# FE_Channel.net
KiCad netlist of a schematic drawn in Altium Designer
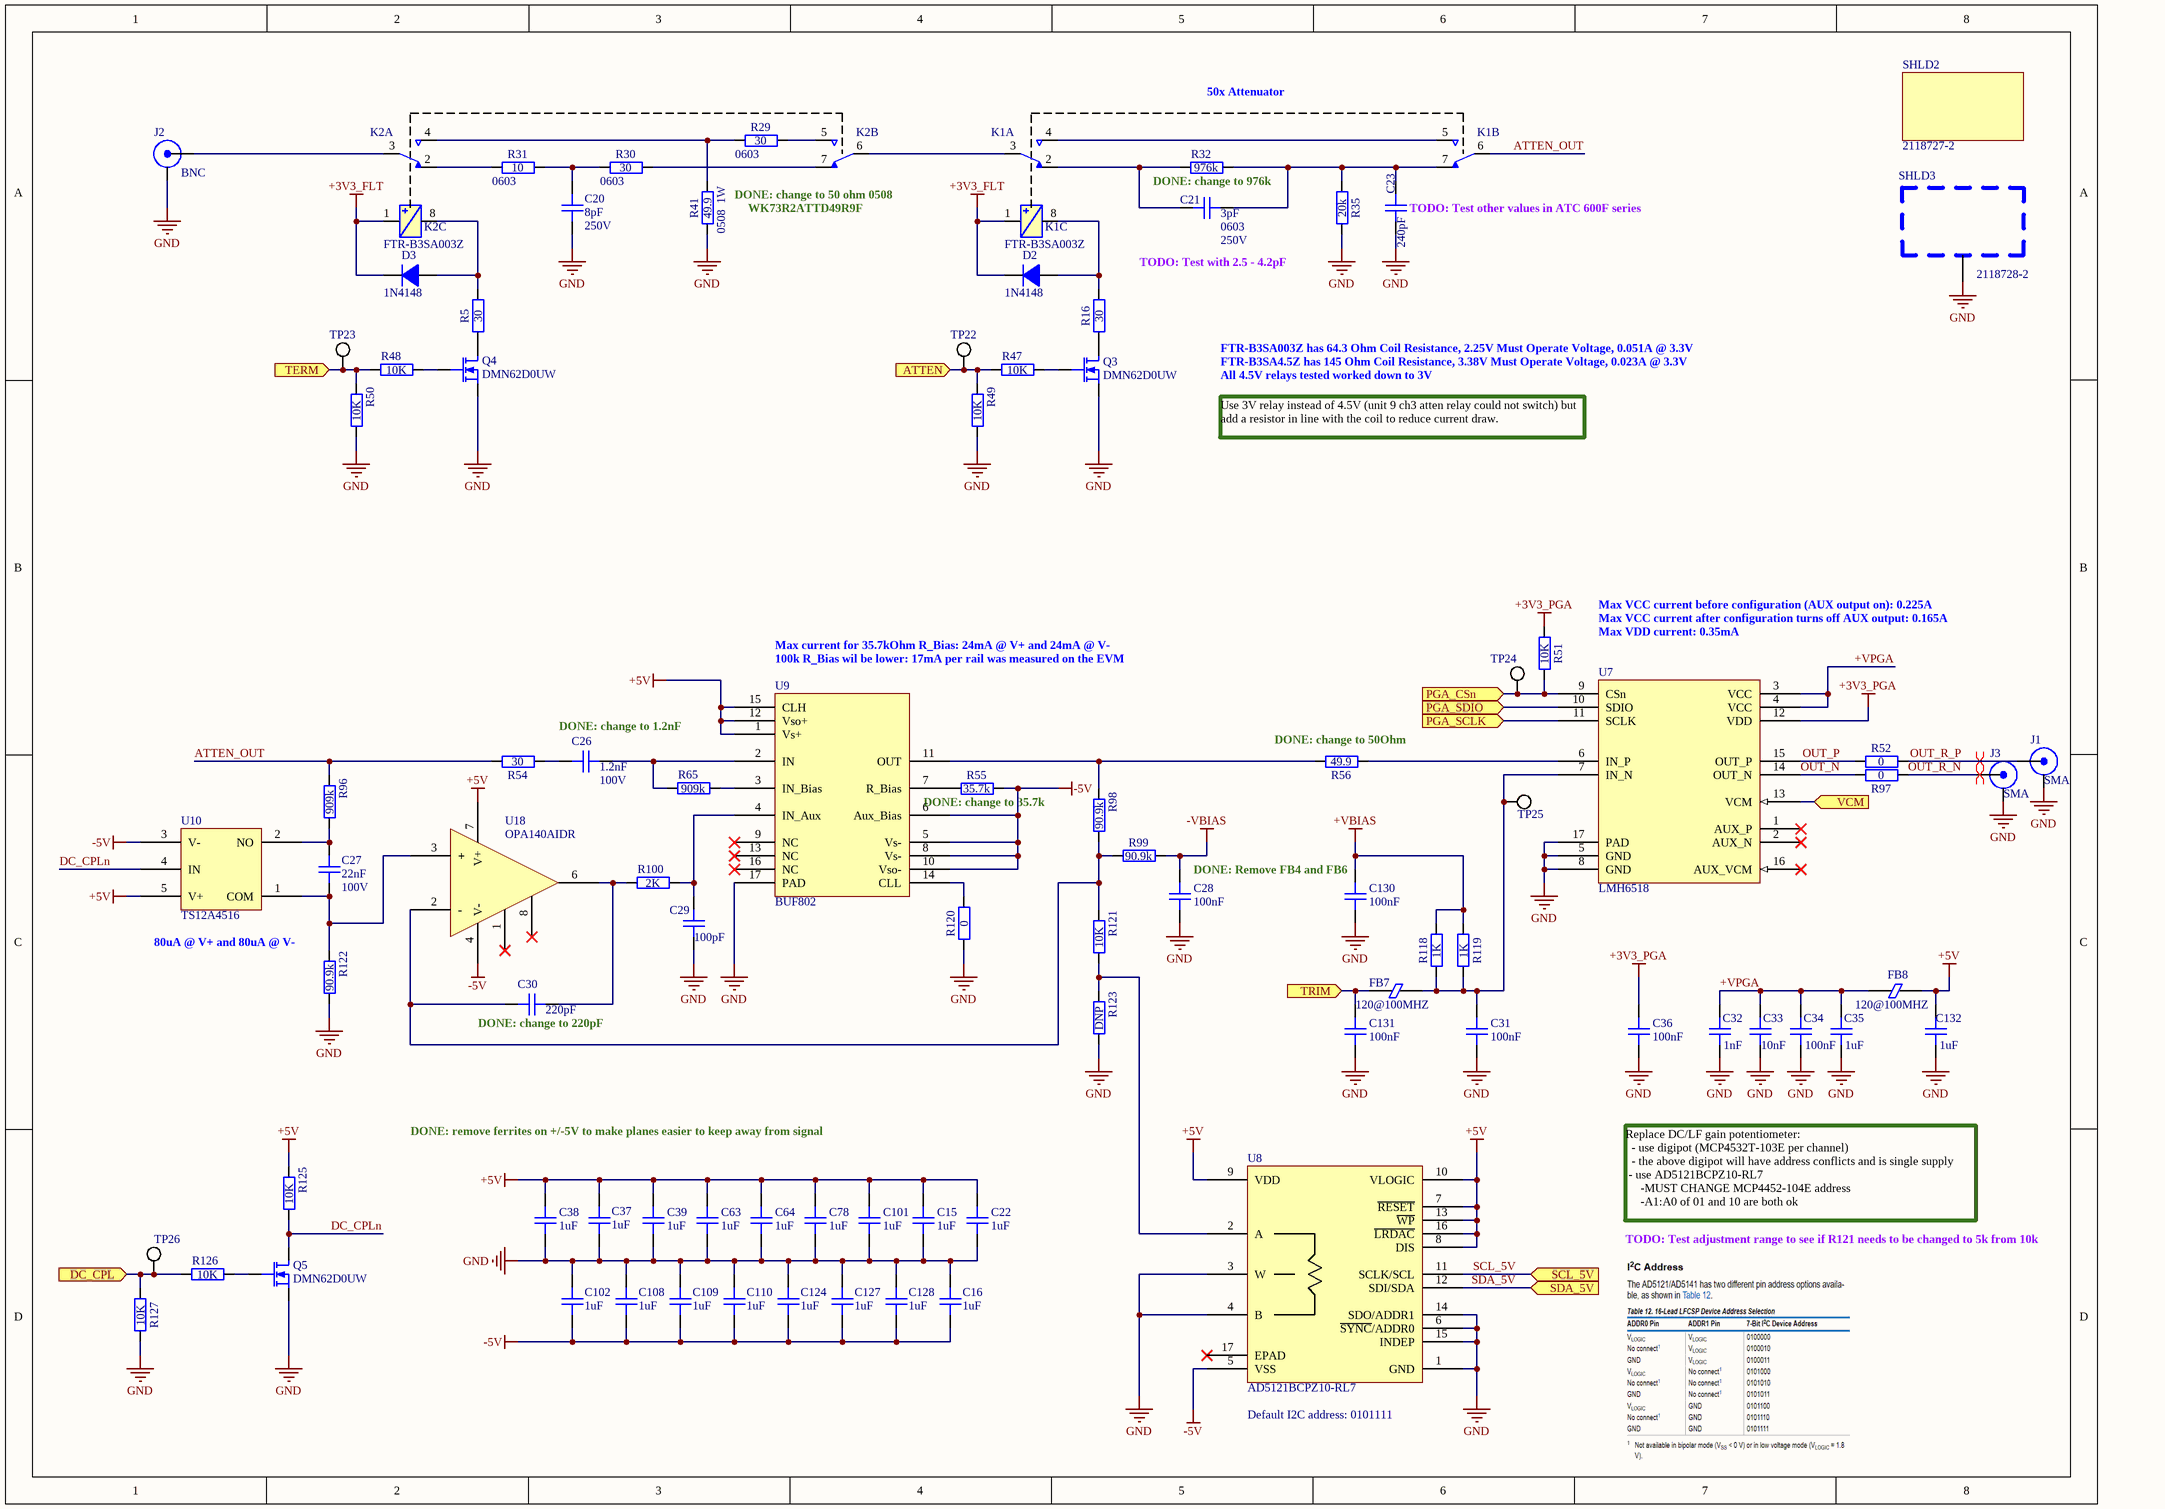
[diagram p0: FE_Channel.SchDoc]

(export (version "E")
  (design (tool "Eeschema 10.0.6"))
  (components
    (comp (ref "C15")
      (value "1uF")
      (footprint "GEN_C_0402")
      (fields
        (field (name "MANUFACTURER") "Murata")
        (field (name "MANUFACTURER PART NUMBER") "GRM155R61E105KA12D")
      )
      (libsource (lib "DSO") (part "CAP 1uF 25V X5R 0402"))
    )
    (comp (ref "C16")
      (value "1uF")
      (footprint "GEN_C_0402")
      (fields
        (field (name "MANUFACTURER") "Murata")
        (field (name "MANUFACTURER PART NUMBER") "GRM155R61E105KA12D")
      )
      (libsource (lib "DSO") (part "CAP 1uF 25V X5R 0402"))
    )
    (comp (ref "C20")
      (value "8pF")
      (footprint "GEN_C_0603")
      (fields
        (field (name "MANUFACTURER") "KEMET")
        (field (name "MANUFACTURER PART NUMBER") "CBR06C809BAGAC")
        (field (name "VOLTAGE RATING") "250V")
      )
      (libsource (lib "DSO") (part "CAP 8pF 250V C0G 0603"))
    )
    (comp (ref "C21")
      (value "3pF")
      (footprint "GEN_C_0603")
      (fields
        (field (name "PACKAGE") "0603")
        (field (name "VOLTAGE RATING") "250V")
        (field (name "MANUFACTURER") "KEMET")
        (field (name "MANUFACTURER PART NUMBER") "CBR06C309BAGAC")
      )
      (libsource (lib "DSO") (part "CAP 3pF 250V C0G 0603"))
    )
    (comp (ref "C22")
      (value "1uF")
      (footprint "GEN_C_0402")
      (fields
        (field (name "MANUFACTURER") "Murata")
        (field (name "MANUFACTURER PART NUMBER") "GRM155R61E105KA12D")
      )
      (libsource (lib "DSO") (part "CAP 1uF 25V X5R 0402"))
    )
    (comp (ref "C23")
      (value "240pF")
      (footprint "GEN_C_0805")
      (fields
        (field (name "MANUFACTURER") "Kyocera AVX")
        (field (name "MANUFACTURER PART NUMBER") "600F241FT250XT")
      )
      (libsource (lib "DSO") (part "CAP 240pF 250V C0G 0805"))
    )
    (comp (ref "C26")
      (value "1.2nF")
      (footprint "GEN_C_0603")
      (fields
        (field (name "VOLTAGE RATING") "100V")
        (field (name "MANUFACTURER") "Murata")
        (field (name "MANUFACTURER PART NUMBER") "GCM1885C2A122FA16D")
      )
      (libsource (lib "DSO") (part "CAP 1.2nF 100V C0G 0603"))
    )
    (comp (ref "C27")
      (value "22nF")
      (footprint "GEN_C_0603")
      (fields
        (field (name "VOLTAGE RATING") "100V")
        (field (name "MANUFACTURER") "Murata")
        (field (name "MANUFACTURER PART NUMBER") "GCM188R72A223KA37D")
      )
      (libsource (lib "DSO") (part "CAP 22nF 100V X7R 0603"))
    )
    (comp (ref "C28")
      (value "100nF")
      (footprint "GEN_C_0402")
      (fields
        (field (name "HOUSE PART NUMBER") "C-100nF-0402-002")
        (field (name "MANUFACTURER") "Murata")
        (field (name "MANUFACTURER PART NUMBER") "GCM155R71C104KA55D")
      )
      (libsource (lib "DSO") (part "CAP 100nF 16V X7R 0402"))
    )
    (comp (ref "C29")
      (value "100pF")
      (footprint "GEN_C_0402")
      (fields
        (field (name "MANUFACTURER") "Murata")
        (field (name "MANUFACTURER PART NUMBER") "GCM1555C1H101FA16D")
      )
      (libsource (lib "DSO") (part "CAP 100pF 50V C0G 0402"))
    )
    (comp (ref "C30")
      (value "220pF")
      (footprint "GEN_C_0402")
      (fields
        (field (name "MANUFACTURER") "Murata")
        (field (name "MANUFACTURER PART NUMBER") "GCM1555C1H221FA16J")
      )
      (libsource (lib "DSO") (part "CAP 220pF 50V C0G 0402"))
    )
    (comp (ref "C31")
      (value "100nF")
      (footprint "GEN_C_0402")
      (fields
        (field (name "HOUSE PART NUMBER") "C-100nF-0402-002")
        (field (name "MANUFACTURER") "Murata")
        (field (name "MANUFACTURER PART NUMBER") "GCM155R71C104KA55D")
      )
      (libsource (lib "DSO") (part "CAP 100nF 16V X7R 0402"))
    )
    (comp (ref "C32")
      (value "1nF")
      (footprint "GEN_C_0402")
      (fields
        (field (name "MANUFACTURER") "Murata")
        (field (name "MANUFACTURER PART NUMBER") "GRM1555C1H102FA01D")
      )
      (libsource (lib "DSO") (part "CAP 1nF 50V C0G 0402"))
    )
    (comp (ref "C33")
      (value "10nF")
      (footprint "GEN_C_0402")
      (fields
        (field (name "HOUSE PART NUMBER") "C-10nF-0402-002")
        (field (name "MANUFACTURER") "Murata")
        (field (name "MANUFACTURER PART NUMBER") "GRM155R71H103KA88J")
      )
      (libsource (lib "DSO") (part "CAP 10nF 50V X7R 0402"))
    )
    (comp (ref "C34")
      (value "100nF")
      (footprint "GEN_C_0402")
      (fields
        (field (name "HOUSE PART NUMBER") "C-100nF-0402-002")
        (field (name "MANUFACTURER") "Murata")
        (field (name "MANUFACTURER PART NUMBER") "GCM155R71C104KA55D")
      )
      (libsource (lib "DSO") (part "CAP 100nF 16V X7R 0402"))
    )
    (comp (ref "C35")
      (value "1uF")
      (footprint "GEN_C_0402")
      (fields
        (field (name "MANUFACTURER") "Murata")
        (field (name "MANUFACTURER PART NUMBER") "GRM155R61E105KA12D")
      )
      (libsource (lib "DSO") (part "CAP 1uF 25V X5R 0402"))
    )
    (comp (ref "C36")
      (value "100nF")
      (footprint "GEN_C_0402")
      (fields
        (field (name "HOUSE PART NUMBER") "C-100nF-0402-002")
        (field (name "MANUFACTURER") "Murata")
        (field (name "MANUFACTURER PART NUMBER") "GCM155R71C104KA55D")
      )
      (libsource (lib "DSO") (part "CAP 100nF 16V X7R 0402"))
    )
    (comp (ref "C37")
      (value "1uF")
      (footprint "GEN_C_0402")
      (fields
        (field (name "MANUFACTURER") "Murata")
        (field (name "MANUFACTURER PART NUMBER") "GRM155R61E105KA12D")
      )
      (libsource (lib "DSO") (part "CAP 1uF 25V X5R 0402"))
    )
    (comp (ref "C38")
      (value "1uF")
      (footprint "GEN_C_0402")
      (fields
        (field (name "MANUFACTURER") "Murata")
        (field (name "MANUFACTURER PART NUMBER") "GRM155R61E105KA12D")
      )
      (libsource (lib "DSO") (part "CAP 1uF 25V X5R 0402"))
    )
    (comp (ref "C39")
      (value "1uF")
      (footprint "GEN_C_0402")
      (fields
        (field (name "MANUFACTURER") "Murata")
        (field (name "MANUFACTURER PART NUMBER") "GRM155R61E105KA12D")
      )
      (libsource (lib "DSO") (part "CAP 1uF 25V X5R 0402"))
    )
    (comp (ref "C63")
      (value "1uF")
      (footprint "GEN_C_0402")
      (fields
        (field (name "MANUFACTURER") "Murata")
        (field (name "MANUFACTURER PART NUMBER") "GRM155R61E105KA12D")
      )
      (libsource (lib "DSO") (part "CAP 1uF 25V X5R 0402"))
    )
    (comp (ref "C64")
      (value "1uF")
      (footprint "GEN_C_0402")
      (fields
        (field (name "MANUFACTURER") "Murata")
        (field (name "MANUFACTURER PART NUMBER") "GRM155R61E105KA12D")
      )
      (libsource (lib "DSO") (part "CAP 1uF 25V X5R 0402"))
    )
    (comp (ref "C78")
      (value "1uF")
      (footprint "GEN_C_0402")
      (fields
        (field (name "MANUFACTURER") "Murata")
        (field (name "MANUFACTURER PART NUMBER") "GRM155R61E105KA12D")
      )
      (libsource (lib "DSO") (part "CAP 1uF 25V X5R 0402"))
    )
    (comp (ref "C101")
      (value "1uF")
      (footprint "GEN_C_0402")
      (fields
        (field (name "MANUFACTURER") "Murata")
        (field (name "MANUFACTURER PART NUMBER") "GRM155R61E105KA12D")
      )
      (libsource (lib "DSO") (part "CAP 1uF 25V X5R 0402"))
    )
    (comp (ref "C102")
      (value "1uF")
      (footprint "GEN_C_0402")
      (fields
        (field (name "MANUFACTURER") "Murata")
        (field (name "MANUFACTURER PART NUMBER") "GRM155R61E105KA12D")
      )
      (libsource (lib "DSO") (part "CAP 1uF 25V X5R 0402"))
    )
    (comp (ref "C108")
      (value "1uF")
      (footprint "GEN_C_0402")
      (fields
        (field (name "MANUFACTURER") "Murata")
        (field (name "MANUFACTURER PART NUMBER") "GRM155R61E105KA12D")
      )
      (libsource (lib "DSO") (part "CAP 1uF 25V X5R 0402"))
    )
    (comp (ref "C109")
      (value "1uF")
      (footprint "GEN_C_0402")
      (fields
        (field (name "MANUFACTURER") "Murata")
        (field (name "MANUFACTURER PART NUMBER") "GRM155R61E105KA12D")
      )
      (libsource (lib "DSO") (part "CAP 1uF 25V X5R 0402"))
    )
    (comp (ref "C110")
      (value "1uF")
      (footprint "GEN_C_0402")
      (fields
        (field (name "MANUFACTURER") "Murata")
        (field (name "MANUFACTURER PART NUMBER") "GRM155R61E105KA12D")
      )
      (libsource (lib "DSO") (part "CAP 1uF 25V X5R 0402"))
    )
    (comp (ref "C124")
      (value "1uF")
      (footprint "GEN_C_0402")
      (fields
        (field (name "MANUFACTURER") "Murata")
        (field (name "MANUFACTURER PART NUMBER") "GRM155R61E105KA12D")
      )
      (libsource (lib "DSO") (part "CAP 1uF 25V X5R 0402"))
    )
    (comp (ref "C127")
      (value "1uF")
      (footprint "GEN_C_0402")
      (fields
        (field (name "MANUFACTURER") "Murata")
        (field (name "MANUFACTURER PART NUMBER") "GRM155R61E105KA12D")
      )
      (libsource (lib "DSO") (part "CAP 1uF 25V X5R 0402"))
    )
    (comp (ref "C128")
      (value "1uF")
      (footprint "GEN_C_0402")
      (fields
        (field (name "MANUFACTURER") "Murata")
        (field (name "MANUFACTURER PART NUMBER") "GRM155R61E105KA12D")
      )
      (libsource (lib "DSO") (part "CAP 1uF 25V X5R 0402"))
    )
    (comp (ref "C130")
      (value "100nF")
      (footprint "GEN_C_0402")
      (fields
        (field (name "HOUSE PART NUMBER") "C-100nF-0402-002")
        (field (name "MANUFACTURER") "Murata")
        (field (name "MANUFACTURER PART NUMBER") "GCM155R71C104KA55D")
      )
      (libsource (lib "DSO") (part "CAP 100nF 16V X7R 0402"))
    )
    (comp (ref "C131")
      (value "100nF")
      (footprint "GEN_C_0402")
      (fields
        (field (name "HOUSE PART NUMBER") "C-100nF-0402-002")
        (field (name "MANUFACTURER") "Murata")
        (field (name "MANUFACTURER PART NUMBER") "GCM155R71C104KA55D")
      )
      (libsource (lib "DSO") (part "CAP 100nF 16V X7R 0402"))
    )
    (comp (ref "C132")
      (value "1uF")
      (footprint "GEN_C_0402")
      (fields
        (field (name "MANUFACTURER") "Murata")
        (field (name "MANUFACTURER PART NUMBER") "GRM155R61E105KA12D")
      )
      (libsource (lib "DSO") (part "CAP 1uF 25V X5R 0402"))
    )
    (comp (ref "D2")
      (value "1N4148")
      (footprint "GEN_SOD_323")
      (fields (field (name "MANUFACTURER") "Diodes") (field (name "MANUFACTURER PART NUMBER") "1N4148WS-7-F"))
      (libsource (lib "DSO") (part "DIODE 1N4148"))
    )
    (comp (ref "D3")
      (value "1N4148")
      (footprint "GEN_SOD_323")
      (fields (field (name "MANUFACTURER") "Diodes") (field (name "MANUFACTURER PART NUMBER") "1N4148WS-7-F"))
      (libsource (lib "DSO") (part "DIODE 1N4148"))
    )
    (comp (ref "FB7")
      (value "120@100MHZ")
      (footprint "GEN_R_0402")
      (fields (field (name "HOUSE PART NUMBER") "BLM15PX121SN1D") (field (name "MANUFACTURER") "Murata"))
      (libsource (lib "DSO") (part "FERRITE BEAD 120 OHM 0402"))
    )
    (comp (ref "FB8")
      (value "120@100MHZ")
      (footprint "GEN_R_0402")
      (fields (field (name "HOUSE PART NUMBER") "BLM15PX121SN1D") (field (name "MANUFACTURER") "Murata"))
      (libsource (lib "DSO") (part "FERRITE BEAD 120 OHM 0402"))
    )
    (comp (ref "J1")
      (value "SMA")
      (footprint "MOL_0733910083")
      (fields (field (name "MANUFACTURER") "Molex") (field (name "MANUFACTURER PART NUMBER") "73100-0105"))
      (libsource (lib "DSO") (part "SMA JACK R/A"))
    )
    (comp (ref "J2")
      (value "BNC")
      (footprint "MOL_0731000105")
      (fields (field (name "MANUFACTURER") "Molex") (field (name "MANUFACTURER PART NUMBER") "73100-0105"))
      (libsource (lib "DSO") (part "BNC JACK R/A"))
    )
    (comp (ref "J3")
      (value "SMA")
      (footprint "MOL_0733910083")
      (fields (field (name "MANUFACTURER") "Molex") (field (name "MANUFACTURER PART NUMBER") "73100-0105"))
      (libsource (lib "DSO") (part "SMA JACK R/A"))
    )
    (comp (ref "K1")
      (value "FTR-B3SA003Z")
      (footprint "FUJ_FTR-B3SA")
      (fields (field (name "MANUFACTURER") "Fujitsu"))
      (libsource (lib "") (part "RELAY DPDT-NO FTR-B3SA003Z_1"))
    )
    (comp (ref "K2")
      (value "FTR-B3SA003Z")
      (footprint "FUJ_FTR-B3SA")
      (fields (field (name "MANUFACTURER") "Fujitsu"))
      (libsource (lib "") (part "RELAY DPDT-NO FTR-B3SA003Z_1"))
    )
    (comp (ref "Q3")
      (value "DMN62D0UW")
      (footprint "GEN_SOT_323")
      (fields (field (name "HOUSE PART NUMBER") "DMN62D0UW-7") (field (name "MANUFACTURER") "Diodes"))
      (libsource (lib "DSO") (part "NMOS DMN62D0UW"))
    )
    (comp (ref "Q4")
      (value "DMN62D0UW")
      (footprint "GEN_SOT_323")
      (fields (field (name "HOUSE PART NUMBER") "DMN62D0UW-7") (field (name "MANUFACTURER") "Diodes"))
      (libsource (lib "DSO") (part "NMOS DMN62D0UW"))
    )
    (comp (ref "Q5")
      (value "DMN62D0UW")
      (footprint "GEN_SOT_323")
      (fields (field (name "HOUSE PART NUMBER") "DMN62D0UW-7") (field (name "MANUFACTURER") "Diodes"))
      (libsource (lib "DSO") (part "NMOS DMN62D0UW"))
    )
    (comp (ref "R5")
      (value "30")
      (footprint "GEN_R_0603")
      (fields
        (field (name "TOLERANCE") "1%")
        (field (name "MANUFACTURER") "KOA Speer")
        (field (name "MANUFACTURER PART NUMBER") "SG73P1JTTD30R0F")
      )
      (libsource (lib "") (part "RES 30 OHM 1% 1/3W 0603_1"))
    )
    (comp (ref "R16")
      (value "30")
      (footprint "GEN_R_0603")
      (fields
        (field (name "TOLERANCE") "1%")
        (field (name "MANUFACTURER") "KOA Speer")
        (field (name "MANUFACTURER PART NUMBER") "SG73P1JTTD30R0F")
      )
      (libsource (lib "") (part "RES 30 OHM 1% 1/3W 0603_1"))
    )
    (comp (ref "R29")
      (value "30")
      (footprint "GEN_R_0603")
      (fields
        (field (name "TOLERANCE") "1%")
        (field (name "PACKAGE") "0603")
        (field (name "MANUFACTURER") "KOA Speer")
        (field (name "MANUFACTURER PART NUMBER") "SG73P1JTTD30R0F")
      )
      (libsource (lib "DSO") (part "RES 30 OHM 1% 1/3W 0603"))
    )
    (comp (ref "R30")
      (value "30")
      (footprint "GEN_R_0603")
      (fields
        (field (name "TOLERANCE") "1%")
        (field (name "PACKAGE") "0603")
        (field (name "MANUFACTURER") "KOA Speer")
        (field (name "MANUFACTURER PART NUMBER") "SG73P1JTTD30R0F")
      )
      (libsource (lib "DSO") (part "RES 30 OHM 1% 1/3W 0603"))
    )
    (comp (ref "R31")
      (value "10")
      (footprint "GEN_R_0603")
      (fields
        (field (name "TOLERANCE") "1%")
        (field (name "PACKAGE") "0603")
        (field (name "MANUFACTURER") "KOA Speer")
        (field (name "MANUFACTURER PART NUMBER") "SG73P1JTTD10R0F")
      )
      (libsource (lib "DSO") (part "RES 10 OHM 1% 1/3W 0603"))
    )
    (comp (ref "R32")
      (value "976k")
      (footprint "GEN_R_0603")
      (fields
        (field (name "MANUFACTURER") "KOA Speer")
        (field (name "MANUFACTURER PART NUMBER") "RK73H1JTTD9763F")
        (field (name "TOLERANCE") "1%")
      )
      (libsource (lib "DSO") (part "RES 976k OHM 1% 1/10W 0603"))
    )
    (comp (ref "R35")
      (value "20k")
      (footprint "GEN_R_0402")
      (fields
        (field (name "TOLERANCE") "1%")
        (field (name "MANUFACTURER") "Yageo")
        (field (name "MANUFACTURER PART NUMBER") "RC0402FR-0720KL")
      )
      (libsource (lib "DSO") (part "RES 20K OHM 1% 1/16W 0402"))
    )
    (comp (ref "R41")
      (value "49.9")
      (footprint "GEN_R_0508")
      (fields
        (field (name "TOLERANCE") "1%")
        (field (name "PACKAGE") "0508")
        (field (name "MANUFACTURER") "KOA Speer")
        (field (name "MANUFACTURER PART NUMBER") "WK73R2ATTD49R9F")
        (field (name "POWER RATING") "1W")
      )
      (libsource (lib "DSO") (part "RES 49.9 OHM 1% 1W 0508"))
    )
    (comp (ref "R47")
      (value "10K")
      (footprint "GEN_R_0402")
      (fields
        (field (name "TOLERANCE") "1%")
        (field (name "MANUFACTURER") "Panasonic")
        (field (name "MANUFACTURER PART NUMBER") "ERJ-2RKF1002X")
      )
      (libsource (lib "") (part "RES 10K OHM 1% 1/10W 0402_1"))
    )
    (comp (ref "R48")
      (value "10K")
      (footprint "GEN_R_0402")
      (fields
        (field (name "TOLERANCE") "1%")
        (field (name "MANUFACTURER") "Panasonic")
        (field (name "MANUFACTURER PART NUMBER") "ERJ-2RKF1002X")
      )
      (libsource (lib "") (part "RES 10K OHM 1% 1/10W 0402_1"))
    )
    (comp (ref "R49")
      (value "10K")
      (footprint "GEN_R_0402")
      (fields
        (field (name "TOLERANCE") "1%")
        (field (name "MANUFACTURER") "Panasonic")
        (field (name "MANUFACTURER PART NUMBER") "ERJ-2RKF1002X")
      )
      (libsource (lib "DSO") (part "RES 10K OHM 1% 1/10W 0402"))
    )
    (comp (ref "R50")
      (value "10K")
      (footprint "GEN_R_0402")
      (fields
        (field (name "TOLERANCE") "1%")
        (field (name "MANUFACTURER") "Panasonic")
        (field (name "MANUFACTURER PART NUMBER") "ERJ-2RKF1002X")
      )
      (libsource (lib "DSO") (part "RES 10K OHM 1% 1/10W 0402"))
    )
    (comp (ref "R51")
      (value "10K")
      (footprint "GEN_R_0402")
      (fields
        (field (name "TOLERANCE") "1%")
        (field (name "MANUFACTURER") "Panasonic")
        (field (name "MANUFACTURER PART NUMBER") "ERJ-2RKF1002X")
      )
      (libsource (lib "DSO") (part "RES 10K OHM 1% 1/10W 0402"))
    )
    (comp (ref "R52")
      (value "0")
      (footprint "GEN_R_0402")
      (fields
        (field (name "MANUFACTURER") "Yageo")
        (field (name "MANUFACTURER PART NUMBER") "RC0402JR-070RL")
      )
      (libsource (lib "") (part "RES 0 OHM 1/16W 0402_1"))
    )
    (comp (ref "R54")
      (value "30")
      (footprint "GEN_R_0603")
      (fields
        (field (name "TOLERANCE") "1%")
        (field (name "MANUFACTURER") "KOA Speer")
        (field (name "MANUFACTURER PART NUMBER") "SG73P1JTTD30R0F")
      )
      (libsource (lib "DSO") (part "RES 30 OHM 1% 1/3W 0603"))
    )
    (comp (ref "R55")
      (value "35.7k")
      (footprint "GEN_R_0402")
      (fields
        (field (name "TOLERANCE") "1%")
        (field (name "MANUFACTURER") "Yageo")
        (field (name "MANUFACTURER PART NUMBER") "RC0402FR-0735K7L")
      )
      (libsource (lib "DSO") (part "RES 35.7K OHM 1% 1/16W 0402"))
    )
    (comp (ref "R56")
      (value "49.9")
      (footprint "GEN_R_0402")
      (fields
        (field (name "MANUFACTURER") "Yageo")
        (field (name "MANUFACTURER PART NUMBER") "RC0402FR-0749R9L")
        (field (name "TOLERANCE") "1%")
      )
      (libsource (lib "DSO") (part "RES 49.9 OHM 1% 1/10W 0402"))
    )
    (comp (ref "R65")
      (value "909k")
      (footprint "GEN_R_0402")
      (fields
        (field (name "TOLERANCE") "1%")
        (field (name "MANUFACTURER") "Yageo")
        (field (name "MANUFACTURER PART NUMBER") "RC0402FR-07909KL")
      )
      (libsource (lib "DSO") (part "RES 909K OHM 1% 1/16W 0402"))
    )
    (comp (ref "R96")
      (value "909k")
      (footprint "GEN_R_0402")
      (fields
        (field (name "TOLERANCE") "1%")
        (field (name "MANUFACTURER") "Yageo")
        (field (name "MANUFACTURER PART NUMBER") "RC0402FR-07909KL")
      )
      (libsource (lib "") (part "RES 909K OHM 1% 1/16W 0402_1"))
    )
    (comp (ref "R97")
      (value "0")
      (footprint "GEN_R_0402")
      (fields
        (field (name "MANUFACTURER") "Yageo")
        (field (name "MANUFACTURER PART NUMBER") "RC0402JR-070RL")
      )
      (libsource (lib "") (part "RES 0 OHM 1/16W 0402_1"))
    )
    (comp (ref "R98")
      (value "90.9k")
      (footprint "GEN_R_0402")
      (fields
        (field (name "TOLERANCE") "1%")
        (field (name "MANUFACTURER") "Yageo")
        (field (name "MANUFACTURER PART NUMBER") "RC0402FR-0790K9L")
      )
      (libsource (lib "") (part "RES 90.9K OHM 1% 1/16W 0402_1"))
    )
    (comp (ref "R99")
      (value "90.9k")
      (footprint "GEN_R_0402")
      (fields
        (field (name "TOLERANCE") "1%")
        (field (name "MANUFACTURER") "Yageo")
        (field (name "MANUFACTURER PART NUMBER") "RC0402FR-0790K9L")
      )
      (libsource (lib "DSO") (part "RES 90.9K OHM 1% 1/16W 0402"))
    )
    (comp (ref "R100")
      (value "2K")
      (footprint "GEN_R_0402")
      (fields
        (field (name "TOLERANCE") "1%")
        (field (name "MANUFACTURER") "Yageo")
        (field (name "MANUFACTURER PART NUMBER") "RC0402FR-072KL")
      )
      (libsource (lib "DSO") (part "RES 2K OHM 1% 1/16W 0402"))
    )
    (comp (ref "R118")
      (value "1K")
      (footprint "GEN_R_0402")
      (fields
        (field (name "TOLERANCE") "1%")
        (field (name "HOUSE PART NUMBER") "R-1K-0402-1%-001")
        (field (name "MANUFACTURER") "Yageo")
      )
      (libsource (lib "") (part "RES 1K OHM 1% 1/10W 0402_1"))
    )
    (comp (ref "R119")
      (value "1K")
      (footprint "GEN_R_0402")
      (fields
        (field (name "TOLERANCE") "1%")
        (field (name "HOUSE PART NUMBER") "R-1K-0402-1%-001")
        (field (name "MANUFACTURER") "Yageo")
      )
      (libsource (lib "DSO") (part "RES 1K OHM 1% 1/10W 0402"))
    )
    (comp (ref "R120")
      (value "0")
      (footprint "GEN_R_0402")
      (fields
        (field (name "MANUFACTURER") "Yageo")
        (field (name "MANUFACTURER PART NUMBER") "RC0402JR-070RL")
      )
      (libsource (lib "DSO") (part "RES 0 OHM 1/16W 0402"))
    )
    (comp (ref "R121")
      (value "10K")
      (footprint "GEN_R_0402")
      (fields
        (field (name "TOLERANCE") "1%")
        (field (name "MANUFACTURER") "Panasonic")
        (field (name "MANUFACTURER PART NUMBER") "ERJ-2RKF1002X")
      )
      (libsource (lib "DSO") (part "RES 10K OHM 1% 1/10W 0402"))
    )
    (comp (ref "R122")
      (value "90.9k")
      (footprint "GEN_R_0402")
      (fields
        (field (name "TOLERANCE") "1%")
        (field (name "MANUFACTURER") "Yageo")
        (field (name "MANUFACTURER PART NUMBER") "RC0402FR-0790K9L")
      )
      (libsource (lib "") (part "RES 90.9K OHM 1% 1/16W 0402_1"))
    )
    (comp (ref "R123")
      (value "DNP")
      (footprint "GEN_R_0402")
      (fields (field (name "TOLERANCE") "1%"))
      (libsource (lib "DSO") (part "RES DNP 0402"))
    )
    (comp (ref "R125")
      (value "10K")
      (footprint "GEN_R_0402")
      (fields
        (field (name "TOLERANCE") "1%")
        (field (name "MANUFACTURER") "Panasonic")
        (field (name "MANUFACTURER PART NUMBER") "ERJ-2RKF1002X")
      )
      (libsource (lib "DSO") (part "RES 10K OHM 1% 1/10W 0402"))
    )
    (comp (ref "R126")
      (value "10K")
      (footprint "GEN_R_0402")
      (fields
        (field (name "TOLERANCE") "1%")
        (field (name "MANUFACTURER") "Panasonic")
        (field (name "MANUFACTURER PART NUMBER") "ERJ-2RKF1002X")
      )
      (libsource (lib "") (part "RES 10K OHM 1% 1/10W 0402_1"))
    )
    (comp (ref "R127")
      (value "10K")
      (footprint "GEN_R_0402")
      (fields
        (field (name "TOLERANCE") "1%")
        (field (name "MANUFACTURER") "Panasonic")
        (field (name "MANUFACTURER PART NUMBER") "ERJ-2RKF1002X")
      )
      (libsource (lib "") (part "RES 10K OHM 1% 1/10W 0402_2"))
    )
    (comp (ref "SHLD2")
      (value "2118727-2")
      (fields (field (name "MANUFACTURER") "TE Connectivity AMP"))
      (libsource (lib "DSO") (part "SHIELD 2118727-2"))
    )
    (comp (ref "SHLD3")
      (value "2118728-2")
      (footprint "TE_2118728-2")
      (fields (field (name "MANUFACTURER") "TE Connectivity"))
      (libsource (lib "DSO") (part "SHIELD 2118728-2"))
    )
    (comp (ref "TP22") (value "PCB") (footprint "GEN_TP_PCB") (libsource (lib "DSO") (part "TP PCB 1mm")))
    (comp (ref "TP23") (value "PCB") (footprint "GEN_TP_PCB") (libsource (lib "DSO") (part "TP PCB 1mm")))
    (comp (ref "TP24") (value "PCB") (footprint "GEN_TP_PCB") (libsource (lib "DSO") (part "TP PCB 1mm")))
    (comp (ref "TP25") (value "PCB") (footprint "GEN_TP_PCB") (libsource (lib "DSO") (part "TP PCB 1mm")))
    (comp (ref "TP26") (value "PCB") (footprint "GEN_TP_PCB") (libsource (lib "DSO") (part "TP PCB 1mm")))
    (comp (ref "U7")
      (value "LMH6518")
      (footprint "TI_WQFN_RGH0016A")
      (fields
        (field (name "MANUFACTURER") "Texas Instruments")
        (field (name "MANUFACTURER PART NUMBER") "LMH6518SQE/NOPB")
      )
      (libsource (lib "DSO") (part "IC PGA LMH6518"))
    )
    (comp (ref "U8")
      (value "AD5121BCPZ10-RL7")
      (footprint "AD_QFN16_CP-16-22")
      (fields (field (name "MANUFACTURER") "Analog Devices"))
      (libsource (lib "DSO") (part "IC DIGIPOT SINGLE AD5121BCPZ10-RL7"))
    )
    (comp (ref "U9")
      (value "BUF802")
      (footprint "TI_VQFN_RGT0016C")
      (fields
        (field (name "MANUFACTURER") "Texas Instruments")
        (field (name "MANUFACTURER PART NUMBER") "BUF802IRGTR")
      )
      (libsource (lib "DSO") (part "IC BUFFER AMP BUF802"))
    )
    (comp (ref "U10")
      (value "TS12A4516")
      (footprint "GEN_SOT23_5_950_2900X1600X1450")
      (fields
        (field (name "MANUFACTURER") "Texas Instruments")
        (field (name "MANUFACTURER PART NUMBER") "TS12A4516DBVR")
      )
      (libsource (lib "DSO") (part "IC SWITCH SPST TS12A4516DBVR"))
    )
    (comp (ref "U18")
      (value "OPA140AIDR")
      (footprint "TI_SOIC8_D0008A")
      (fields (field (name "MANUFACTURER") "Texas Instruments"))
      (libsource (lib "DSO") (part "IC OPAMP OPA140"))
    )
  )
  (nets
    (net (code "1") (name "+3V3_FLT") (class "Default")
      (node (ref "D2") (pin "1") (pinfunction "K_1") (pintype "passive"))
      (node (ref "D3") (pin "1") (pinfunction "K_1") (pintype "passive"))
      (node (ref "K1") (pin "1") (pinfunction "1_1") (pintype "passive"))
      (node (ref "K2") (pin "1") (pinfunction "1_1") (pintype "passive"))
    )
    (net (code "2") (name "+3V3_PGA") (class "Default")
      (node (ref "C36") (pin "2") (pinfunction "2_2") (pintype "passive"))
      (node (ref "R51") (pin "2") (pinfunction "2_2") (pintype "passive"))
      (node (ref "U7") (pin "12") (pinfunction "VDD_12") (pintype "power_in"))
    )
    (net (code "3") (name "+5V") (class "Default")
      (node (ref "C101") (pin "2") (pinfunction "2_2") (pintype "passive"))
      (node (ref "C132") (pin "2") (pinfunction "2_2") (pintype "passive"))
      (node (ref "C15") (pin "2") (pinfunction "2_2") (pintype "passive"))
      (node (ref "C22") (pin "2") (pinfunction "2_2") (pintype "passive"))
      (node (ref "C37") (pin "2") (pinfunction "2_2") (pintype "passive"))
      (node (ref "C38") (pin "1") (pinfunction "1_1") (pintype "passive"))
      (node (ref "C39") (pin "1") (pinfunction "1_1") (pintype "passive"))
      (node (ref "C63") (pin "1") (pinfunction "1_1") (pintype "passive"))
      (node (ref "C64") (pin "2") (pinfunction "2_2") (pintype "passive"))
      (node (ref "C78") (pin "2") (pinfunction "2_2") (pintype "passive"))
      (node (ref "FB8") (pin "2") (pinfunction "2_2") (pintype "passive"))
      (node (ref "R125") (pin "2") (pinfunction "2_2") (pintype "passive"))
      (node (ref "U10") (pin "5") (pinfunction "V+_5") (pintype "passive"))
      (node (ref "U18") (pin "7") (pinfunction "V+_7") (pintype "passive"))
      (node (ref "U8") (pin "10") (pinfunction "VLOGIC_10") (pintype "passive"))
      (node (ref "U8") (pin "13") (pinfunction "~{WP}_13") (pintype "passive"))
      (node (ref "U8") (pin "16") (pinfunction "~{LRDAC}_16") (pintype "passive"))
      (node (ref "U8") (pin "7") (pinfunction "~{RESET}_7") (pintype "passive"))
      (node (ref "U8") (pin "8") (pinfunction "DIS_8") (pintype "passive"))
      (node (ref "U8") (pin "9") (pinfunction "VDD_9") (pintype "passive"))
      (node (ref "U9") (pin "1") (pinfunction "Vs+_1") (pintype "passive"))
      (node (ref "U9") (pin "12") (pinfunction "Vso+_12") (pintype "passive"))
      (node (ref "U9") (pin "15") (pinfunction "CLH_15") (pintype "passive"))
    )
    (net (code "4") (name "+VBIAS") (class "Default")
      (node (ref "C130") (pin "1") (pinfunction "1_1") (pintype "passive"))
      (node (ref "R118") (pin "2") (pinfunction "2_2") (pintype "passive"))
      (node (ref "R119") (pin "1") (pinfunction "1_1") (pintype "passive"))
    )
    (net (code "5") (name "-5V") (class "Default")
      (node (ref "C102") (pin "2") (pinfunction "2_2") (pintype "passive"))
      (node (ref "C108") (pin "2") (pinfunction "2_2") (pintype "passive"))
      (node (ref "C109") (pin "1") (pinfunction "1_1") (pintype "passive"))
      (node (ref "C110") (pin "1") (pinfunction "1_1") (pintype "passive"))
      (node (ref "C124") (pin "1") (pinfunction "1_1") (pintype "passive"))
      (node (ref "C127") (pin "2") (pinfunction "2_2") (pintype "passive"))
      (node (ref "C128") (pin "2") (pinfunction "2_2") (pintype "passive"))
      (node (ref "C16") (pin "2") (pinfunction "2_2") (pintype "passive"))
      (node (ref "R55") (pin "2") (pinfunction "2_2") (pintype "passive"))
      (node (ref "U10") (pin "3") (pinfunction "V-_3") (pintype "passive"))
      (node (ref "U18") (pin "4") (pinfunction "V-_4") (pintype "passive"))
      (node (ref "U8") (pin "5") (pinfunction "VSS_5") (pintype "passive"))
      (node (ref "U9") (pin "10") (pinfunction "Vso-_10") (pintype "passive"))
      (node (ref "U9") (pin "5") (pinfunction "Vs-_5") (pintype "passive"))
      (node (ref "U9") (pin "6") (pinfunction "Aux_Bias_6") (pintype "passive"))
      (node (ref "U9") (pin "8") (pinfunction "Vs-_8") (pintype "passive"))
    )
    (net (code "6") (name "-VBIAS") (class "Default")
      (node (ref "C28") (pin "1") (pinfunction "1_1") (pintype "passive"))
      (node (ref "R99") (pin "1") (pinfunction "1_1") (pintype "passive"))
    )
    (net (code "7") (name "/+VPGA") (class "Default")
      (node (ref "C32") (pin "2") (pinfunction "2_2") (pintype "passive"))
      (node (ref "C33") (pin "2") (pinfunction "2_2") (pintype "passive"))
      (node (ref "C34") (pin "2") (pinfunction "2_2") (pintype "passive"))
      (node (ref "C35") (pin "2") (pinfunction "2_2") (pintype "passive"))
      (node (ref "FB8") (pin "1") (pinfunction "1_1") (pintype "passive"))
      (node (ref "U7") (pin "3") (pinfunction "VCC_3") (pintype "power_in"))
      (node (ref "U7") (pin "4") (pinfunction "VCC_4") (pintype "power_in"))
    )
    (net (code "8") (name "/ATTEN") (class "Default")
      (node (ref "R47") (pin "2") (pinfunction "2_2") (pintype "passive"))
      (node (ref "R49") (pin "2") (pinfunction "2_2") (pintype "passive"))
      (node (ref "TP22") (pin "1") (pinfunction "1_1") (pintype "passive"))
    )
    (net (code "9") (name "/ATTEN_OUT") (class "Default")
      (node (ref "K1") (pin "6") (pinfunction "6_6") (pintype "passive"))
      (node (ref "R54") (pin "1") (pinfunction "1_1") (pintype "passive"))
      (node (ref "R96") (pin "2") (pinfunction "2_2") (pintype "passive"))
    )
    (net (code "10") (name "/DC_CPL") (class "Default")
      (node (ref "R126") (pin "2") (pinfunction "2_2") (pintype "passive"))
      (node (ref "R127") (pin "2") (pinfunction "2_2") (pintype "passive"))
      (node (ref "TP26") (pin "1") (pinfunction "1_1") (pintype "passive"))
    )
    (net (code "11") (name "/DC_CPLn") (class "Default")
      (node (ref "Q5") (pin "1") (pinfunction "D_1") (pintype "passive"))
      (node (ref "R125") (pin "1") (pinfunction "1_1") (pintype "passive"))
      (node (ref "U10") (pin "4") (pinfunction "IN_4") (pintype "passive"))
    )
    (net (code "12") (name "/OUT_N") (class "Default")
      (node (ref "R97") (pin "1") (pinfunction "1_1") (pintype "passive"))
      (node (ref "U7") (pin "14") (pinfunction "OUT_N_14") (pintype "passive"))
    )
    (net (code "13") (name "/OUT_P") (class "Default")
      (node (ref "R52") (pin "1") (pinfunction "1_1") (pintype "passive"))
      (node (ref "U7") (pin "15") (pinfunction "OUT_P_15") (pintype "passive"))
    )
    (net (code "14") (name "/OUT_R_N") (class "Default")
      (node (ref "J3") (pin "1") (pinfunction "Signal_1") (pintype "passive"))
      (node (ref "R97") (pin "2") (pinfunction "2_2") (pintype "passive"))
    )
    (net (code "15") (name "/OUT_R_P") (class "Default")
      (node (ref "J1") (pin "1") (pinfunction "Signal_1") (pintype "passive"))
      (node (ref "R52") (pin "2") (pinfunction "2_2") (pintype "passive"))
    )
    (net (code "16") (name "/PGA_CSn") (class "Default")
      (node (ref "R51") (pin "1") (pinfunction "1_1") (pintype "passive"))
      (node (ref "TP24") (pin "1") (pinfunction "1_1") (pintype "passive"))
      (node (ref "U7") (pin "9") (pinfunction "CSn_9") (pintype "passive"))
    )
    (net (code "17") (name "/PGA_SCLK") (class "Default")
      (node (ref "U7") (pin "11") (pinfunction "SCLK_11") (pintype "passive"))
    )
    (net (code "18") (name "/PGA_SDIO") (class "Default")
      (node (ref "U7") (pin "10") (pinfunction "SDIO_10") (pintype "passive"))
    )
    (net (code "19") (name "/SCL_5V") (class "Default")
      (node (ref "U8") (pin "11") (pinfunction "SCLK/SCL_11") (pintype "passive"))
    )
    (net (code "20") (name "/SDA_5V") (class "Default")
      (node (ref "U8") (pin "12") (pinfunction "SDI/SDA_12") (pintype "passive"))
    )
    (net (code "21") (name "/TERM") (class "Default")
      (node (ref "R48") (pin "2") (pinfunction "2_2") (pintype "passive"))
      (node (ref "R50") (pin "2") (pinfunction "2_2") (pintype "passive"))
      (node (ref "TP23") (pin "1") (pinfunction "1_1") (pintype "passive"))
    )
    (net (code "22") (name "/TRIM") (class "Default")
      (node (ref "C131") (pin "1") (pinfunction "1_1") (pintype "passive"))
      (node (ref "FB7") (pin "1") (pinfunction "1_1") (pintype "passive"))
    )
    (net (code "23") (name "/VCM") (class "Default")
      (node (ref "U7") (pin "13") (pinfunction "VCM_13") (pintype "input"))
    )
    (net (code "24") (name "GND") (class "Default")
      (node (ref "C101") (pin "1") (pinfunction "1_1") (pintype "passive"))
      (node (ref "C102") (pin "1") (pinfunction "1_1") (pintype "passive"))
      (node (ref "C108") (pin "1") (pinfunction "1_1") (pintype "passive"))
      (node (ref "C109") (pin "2") (pinfunction "2_2") (pintype "passive"))
      (node (ref "C110") (pin "2") (pinfunction "2_2") (pintype "passive"))
      (node (ref "C124") (pin "2") (pinfunction "2_2") (pintype "passive"))
      (node (ref "C127") (pin "1") (pinfunction "1_1") (pintype "passive"))
      (node (ref "C128") (pin "1") (pinfunction "1_1") (pintype "passive"))
      (node (ref "C130") (pin "2") (pinfunction "2_2") (pintype "passive"))
      (node (ref "C131") (pin "2") (pinfunction "2_2") (pintype "passive"))
      (node (ref "C132") (pin "1") (pinfunction "1_1") (pintype "passive"))
      (node (ref "C15") (pin "1") (pinfunction "1_1") (pintype "passive"))
      (node (ref "C16") (pin "1") (pinfunction "1_1") (pintype "passive"))
      (node (ref "C20") (pin "2") (pinfunction "2_2") (pintype "passive"))
      (node (ref "C22") (pin "1") (pinfunction "1_1") (pintype "passive"))
      (node (ref "C23") (pin "1") (pinfunction "1_1") (pintype "passive"))
      (node (ref "C28") (pin "2") (pinfunction "2_2") (pintype "passive"))
      (node (ref "C29") (pin "1") (pinfunction "1_1") (pintype "passive"))
      (node (ref "C31") (pin "2") (pinfunction "2_2") (pintype "passive"))
      (node (ref "C32") (pin "1") (pinfunction "1_1") (pintype "passive"))
      (node (ref "C33") (pin "1") (pinfunction "1_1") (pintype "passive"))
      (node (ref "C34") (pin "1") (pinfunction "1_1") (pintype "passive"))
      (node (ref "C35") (pin "1") (pinfunction "1_1") (pintype "passive"))
      (node (ref "C36") (pin "1") (pinfunction "1_1") (pintype "passive"))
      (node (ref "C37") (pin "1") (pinfunction "1_1") (pintype "passive"))
      (node (ref "C38") (pin "2") (pinfunction "2_2") (pintype "passive"))
      (node (ref "C39") (pin "2") (pinfunction "2_2") (pintype "passive"))
      (node (ref "C63") (pin "2") (pinfunction "2_2") (pintype "passive"))
      (node (ref "C64") (pin "1") (pinfunction "1_1") (pintype "passive"))
      (node (ref "C78") (pin "1") (pinfunction "1_1") (pintype "passive"))
      (node (ref "J1") (pin "2") (pinfunction "SHIELD_2") (pintype "passive"))
      (node (ref "J2") (pin "2") (pinfunction "SHIELD_2") (pintype "passive"))
      (node (ref "J3") (pin "2") (pinfunction "SHIELD_2") (pintype "passive"))
      (node (ref "Q3") (pin "3") (pinfunction "S_3") (pintype "passive"))
      (node (ref "Q4") (pin "3") (pinfunction "S_3") (pintype "passive"))
      (node (ref "Q5") (pin "3") (pinfunction "S_3") (pintype "passive"))
      (node (ref "R120") (pin "1") (pinfunction "1_1") (pintype "passive"))
      (node (ref "R122") (pin "1") (pinfunction "1_1") (pintype "passive"))
      (node (ref "R123") (pin "1") (pinfunction "1_1") (pintype "passive"))
      (node (ref "R127") (pin "1") (pinfunction "1_1") (pintype "passive"))
      (node (ref "R35") (pin "1") (pinfunction "1_1") (pintype "passive"))
      (node (ref "R41") (pin "1") (pinfunction "1_1") (pintype "passive"))
      (node (ref "R49") (pin "1") (pinfunction "1_1") (pintype "passive"))
      (node (ref "R50") (pin "1") (pinfunction "1_1") (pintype "passive"))
      (node (ref "SHLD3") (pin "1") (pinfunction "1_1") (pintype "passive"))
      (node (ref "U7") (pin "17") (pinfunction "PAD_17") (pintype "power_in"))
      (node (ref "U7") (pin "5") (pinfunction "GND_5") (pintype "power_in"))
      (node (ref "U7") (pin "8") (pinfunction "GND_8") (pintype "power_in"))
      (node (ref "U8") (pin "1") (pinfunction "GND_1") (pintype "passive"))
      (node (ref "U8") (pin "14") (pinfunction "SDO/ADDR1_14") (pintype "passive"))
      (node (ref "U8") (pin "15") (pinfunction "INDEP_15") (pintype "passive"))
      (node (ref "U8") (pin "3") (pinfunction "W_3") (pintype "passive"))
      (node (ref "U8") (pin "4") (pinfunction "B_4") (pintype "passive"))
      (node (ref "U8") (pin "6") (pinfunction "~{SYNC}/ADDR0_6") (pintype "passive"))
      (node (ref "U9") (pin "17") (pinfunction "PAD_17") (pintype "passive"))
    )
    (net (code "25") (name "Net-(C20-Pad1)") (class "Default")
      (node (ref "C20") (pin "1") (pinfunction "1_1") (pintype "passive"))
      (node (ref "R30") (pin "1") (pinfunction "1_1") (pintype "passive"))
      (node (ref "R31") (pin "2") (pinfunction "2_2") (pintype "passive"))
    )
    (net (code "26") (name "Net-(C21-Pad1)") (class "Default")
      (node (ref "C21") (pin "1") (pinfunction "1_1") (pintype "passive"))
      (node (ref "C23") (pin "2") (pinfunction "2_2") (pintype "passive"))
      (node (ref "K1") (pin "7") (pinfunction "7_7") (pintype "passive"))
      (node (ref "R32") (pin "2") (pinfunction "2_2") (pintype "passive"))
      (node (ref "R35") (pin "2") (pinfunction "2_2") (pintype "passive"))
    )
    (net (code "27") (name "Net-(C21-Pad2)") (class "Default")
      (node (ref "C21") (pin "2") (pinfunction "2_2") (pintype "passive"))
      (node (ref "K1") (pin "2") (pinfunction "2_2") (pintype "passive"))
      (node (ref "R32") (pin "1") (pinfunction "1_1") (pintype "passive"))
    )
    (net (code "28") (name "Net-(C26-Pad2)") (class "Default")
      (node (ref "C26") (pin "2") (pinfunction "2_2") (pintype "passive"))
      (node (ref "R54") (pin "2") (pinfunction "2_2") (pintype "passive"))
    )
    (net (code "29") (name "Net-(D2-A)") (class "Default")
      (node (ref "D2") (pin "2") (pinfunction "A_2") (pintype "passive"))
      (node (ref "K1") (pin "8") (pinfunction "8_8") (pintype "passive"))
      (node (ref "R16") (pin "2") (pinfunction "2_2") (pintype "passive"))
    )
    (net (code "30") (name "Net-(D3-A)") (class "Default")
      (node (ref "D3") (pin "2") (pinfunction "A_2") (pintype "passive"))
      (node (ref "K2") (pin "8") (pinfunction "8_8") (pintype "passive"))
      (node (ref "R5") (pin "2") (pinfunction "2_2") (pintype "passive"))
    )
    (net (code "31") (name "Net-(J2-Signal)") (class "Default")
      (node (ref "J2") (pin "1") (pinfunction "Signal_1") (pintype "passive"))
      (node (ref "K2") (pin "3") (pinfunction "3_3") (pintype "passive"))
    )
    (net (code "32") (name "Net-(K1-Pad3)") (class "Default")
      (node (ref "K1") (pin "3") (pinfunction "3_3") (pintype "passive"))
      (node (ref "K2") (pin "6") (pinfunction "6_6") (pintype "passive"))
    )
    (net (code "33") (name "Net-(K1-Pad4)") (class "Default")
      (node (ref "K1") (pin "4") (pinfunction "4_4") (pintype "passive"))
      (node (ref "K1") (pin "5") (pinfunction "5_5") (pintype "passive"))
    )
    (net (code "34") (name "Net-(K2-Pad2)") (class "Default")
      (node (ref "K2") (pin "2") (pinfunction "2_2") (pintype "passive"))
      (node (ref "R31") (pin "1") (pinfunction "1_1") (pintype "passive"))
    )
    (net (code "35") (name "Net-(K2-Pad4)") (class "Default")
      (node (ref "K2") (pin "4") (pinfunction "4_4") (pintype "passive"))
      (node (ref "R29") (pin "1") (pinfunction "1_1") (pintype "passive"))
      (node (ref "R41") (pin "2") (pinfunction "2_2") (pintype "passive"))
    )
    (net (code "36") (name "Net-(K2-Pad5)") (class "Default")
      (node (ref "K2") (pin "5") (pinfunction "5_5") (pintype "passive"))
      (node (ref "R29") (pin "2") (pinfunction "2_2") (pintype "passive"))
    )
    (net (code "37") (name "Net-(K2-Pad7)") (class "Default")
      (node (ref "K2") (pin "7") (pinfunction "7_7") (pintype "passive"))
      (node (ref "R30") (pin "2") (pinfunction "2_2") (pintype "passive"))
    )
    (net (code "38") (name "Net-(Q3-D)") (class "Default")
      (node (ref "Q3") (pin "1") (pinfunction "D_1") (pintype "passive"))
      (node (ref "R16") (pin "1") (pinfunction "1_1") (pintype "passive"))
    )
    (net (code "39") (name "Net-(Q3-G)") (class "Default")
      (node (ref "Q3") (pin "2") (pinfunction "G_2") (pintype "passive"))
      (node (ref "R47") (pin "1") (pinfunction "1_1") (pintype "passive"))
    )
    (net (code "40") (name "Net-(Q4-D)") (class "Default")
      (node (ref "Q4") (pin "1") (pinfunction "D_1") (pintype "passive"))
      (node (ref "R5") (pin "1") (pinfunction "1_1") (pintype "passive"))
    )
    (net (code "41") (name "Net-(Q4-G)") (class "Default")
      (node (ref "Q4") (pin "2") (pinfunction "G_2") (pintype "passive"))
      (node (ref "R48") (pin "1") (pinfunction "1_1") (pintype "passive"))
    )
    (net (code "42") (name "Net-(Q5-G)") (class "Default")
      (node (ref "Q5") (pin "2") (pinfunction "G_2") (pintype "passive"))
      (node (ref "R126") (pin "1") (pinfunction "1_1") (pintype "passive"))
    )
    (net (code "43") (name "Net-(U7-IN_N)") (class "Default")
      (node (ref "C31") (pin "1") (pinfunction "1_1") (pintype "passive"))
      (node (ref "FB7") (pin "2") (pinfunction "2_2") (pintype "passive"))
      (node (ref "R118") (pin "1") (pinfunction "1_1") (pintype "passive"))
      (node (ref "R119") (pin "2") (pinfunction "2_2") (pintype "passive"))
      (node (ref "TP25") (pin "1") (pinfunction "1_1") (pintype "passive"))
      (node (ref "U7") (pin "7") (pinfunction "IN_N_7") (pintype "passive"))
    )
    (net (code "44") (name "Net-(U7-IN_P)") (class "Default")
      (node (ref "R56") (pin "2") (pinfunction "2_2") (pintype "passive"))
      (node (ref "U7") (pin "6") (pinfunction "IN_P_6") (pintype "passive"))
    )
    (net (code "45") (name "Net-(U8-A)") (class "Default")
      (node (ref "R121") (pin "1") (pinfunction "1_1") (pintype "passive"))
      (node (ref "R123") (pin "2") (pinfunction "2_2") (pintype "passive"))
      (node (ref "U8") (pin "2") (pinfunction "A_2") (pintype "passive"))
    )
    (net (code "46") (name "Net-(U9-CLL)") (class "Default")
      (node (ref "R120") (pin "2") (pinfunction "2_2") (pintype "passive"))
      (node (ref "U9") (pin "14") (pinfunction "CLL_14") (pintype "passive"))
    )
    (net (code "47") (name "Net-(U9-IN)") (class "Default")
      (node (ref "C26") (pin "1") (pinfunction "1_1") (pintype "passive"))
      (node (ref "R65") (pin "2") (pinfunction "2_2") (pintype "passive"))
      (node (ref "U9") (pin "2") (pinfunction "IN_2") (pintype "passive"))
    )
    (net (code "48") (name "Net-(U9-IN_Aux)") (class "Default")
      (node (ref "C29") (pin "2") (pinfunction "2_2") (pintype "passive"))
      (node (ref "R100") (pin "1") (pinfunction "1_1") (pintype "passive"))
      (node (ref "U9") (pin "4") (pinfunction "IN_Aux_4") (pintype "passive"))
    )
    (net (code "49") (name "Net-(U9-IN_Bias)") (class "Default")
      (node (ref "R65") (pin "1") (pinfunction "1_1") (pintype "passive"))
      (node (ref "U9") (pin "3") (pinfunction "IN_Bias_3") (pintype "passive"))
    )
    (net (code "50") (name "Net-(U9-OUT)") (class "Default")
      (node (ref "R56") (pin "1") (pinfunction "1_1") (pintype "passive"))
      (node (ref "R98") (pin "2") (pinfunction "2_2") (pintype "passive"))
      (node (ref "U9") (pin "11") (pinfunction "OUT_11") (pintype "passive"))
    )
    (net (code "51") (name "Net-(U9-R_Bias)") (class "Default")
      (node (ref "R55") (pin "1") (pinfunction "1_1") (pintype "passive"))
      (node (ref "U9") (pin "7") (pinfunction "R_Bias_7") (pintype "passive"))
    )
    (net (code "52") (name "Net-(U10-COM)") (class "Default")
      (node (ref "C27") (pin "2") (pinfunction "2_2") (pintype "passive"))
      (node (ref "R122") (pin "2") (pinfunction "2_2") (pintype "passive"))
      (node (ref "U10") (pin "1") (pinfunction "COM_1") (pintype "passive"))
      (node (ref "U18") (pin "3") (pinfunction "+_3") (pintype "passive"))
    )
    (net (code "53") (name "Net-(U10-NO)") (class "Default")
      (node (ref "C27") (pin "1") (pinfunction "1_1") (pintype "passive"))
      (node (ref "R96") (pin "1") (pinfunction "1_1") (pintype "passive"))
      (node (ref "U10") (pin "2") (pinfunction "NO_2") (pintype "passive"))
    )
    (net (code "54") (name "Net-(U18--)") (class "Default")
      (node (ref "C30") (pin "2") (pinfunction "2_2") (pintype "passive"))
      (node (ref "R121") (pin "2") (pinfunction "2_2") (pintype "passive"))
      (node (ref "R98") (pin "1") (pinfunction "1_1") (pintype "passive"))
      (node (ref "R99") (pin "2") (pinfunction "2_2") (pintype "passive"))
      (node (ref "U18") (pin "2") (pinfunction "-_2") (pintype "passive"))
    )
    (net (code "55") (name "Net-(U18-OUT)") (class "Default")
      (node (ref "C30") (pin "1") (pinfunction "1_1") (pintype "passive"))
      (node (ref "R100") (pin "2") (pinfunction "2_2") (pintype "passive"))
      (node (ref "U18") (pin "6") (pinfunction "OUT_6") (pintype "passive"))
    )
    (net (code "56") (name "unconnected-(U7-AUX_N-Pad2)") (class "Default")
      (node (ref "U7") (pin "2") (pinfunction "AUX_N_2") (pintype "passive+no_connect"))
    )
    (net (code "57") (name "unconnected-(U7-AUX_P-Pad1)") (class "Default")
      (node (ref "U7") (pin "1") (pinfunction "AUX_P_1") (pintype "passive+no_connect"))
    )
    (net (code "58") (name "unconnected-(U7-AUX_VCM-Pad16)") (class "Default")
      (node (ref "U7") (pin "16") (pinfunction "AUX_VCM_16") (pintype "input+no_connect"))
    )
    (net (code "59") (name "unconnected-(U8-EPAD-Pad17)") (class "Default")
      (node (ref "U8") (pin "17") (pinfunction "EPAD_17") (pintype "passive+no_connect"))
    )
    (net (code "60") (name "unconnected-(U9-NC-Pad9)") (class "Default")
      (node (ref "U9") (pin "9") (pinfunction "NC_9") (pintype "passive+no_connect"))
    )
    (net (code "61") (name "unconnected-(U9-NC-Pad13)") (class "Default")
      (node (ref "U9") (pin "13") (pinfunction "NC_13") (pintype "passive+no_connect"))
    )
    (net (code "62") (name "unconnected-(U9-NC-Pad16)") (class "Default")
      (node (ref "U9") (pin "16") (pinfunction "NC_16") (pintype "passive+no_connect"))
    )
    (net (code "63") (name "unconnected-(U18-N1-Pad1)") (class "Default")
      (node (ref "U18") (pin "1") (pinfunction "N1_1") (pintype "passive+no_connect"))
    )
    (net (code "64") (name "unconnected-(U18-N2-Pad8)") (class "Default")
      (node (ref "U18") (pin "8") (pinfunction "N2_8") (pintype "passive+no_connect"))
    )
  )
)
